# klon.net
KiCad netlist of a schematic drawn in EAGLE
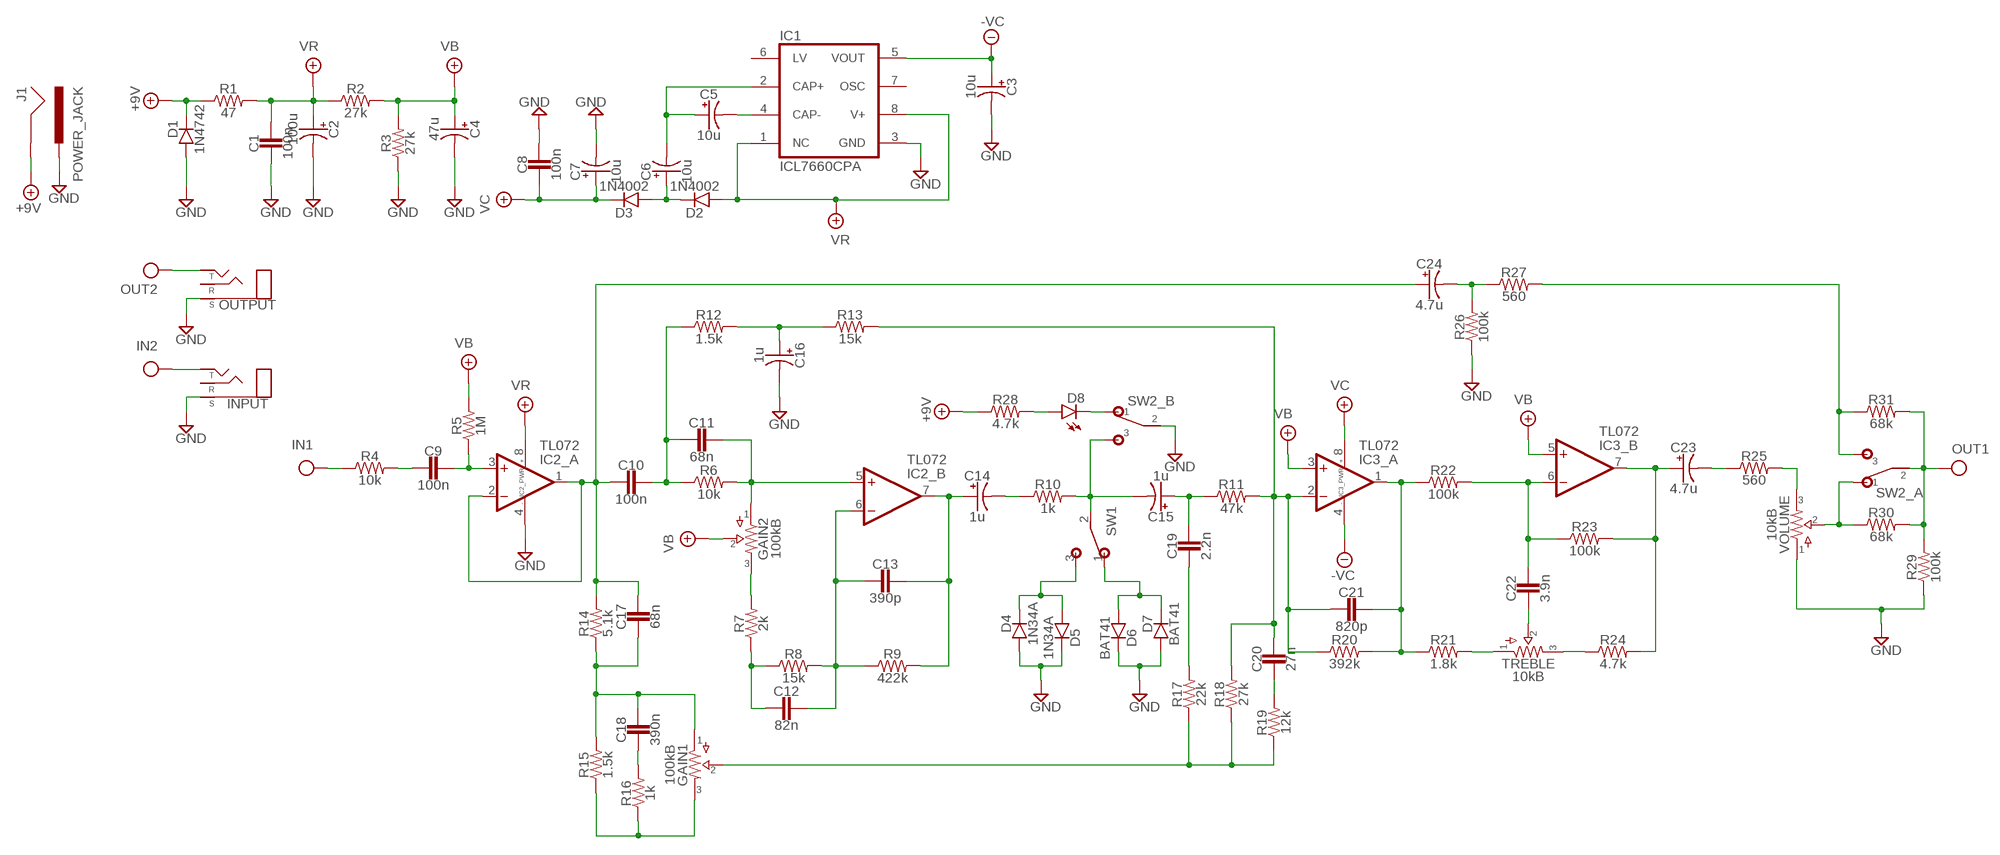
[diagram p0: schematic, sheet 1]

(export (version "E")
  (design (tool "Eeschema 10.0.6"))
  (components
    (comp (ref "C1")
      (value "100n")
      (footprint "eagle-import:050X030_025_2")
      (libsource (lib "eagle-import") (part "CER/FILM2"))
    )
    (comp (ref "C2")
      (value "100u")
      (footprint "eagle-import:050_020")
      (libsource (lib "eagle-import") (part "0500"))
    )
    (comp (ref "C3")
      (value "10u")
      (footprint "eagle-import:050_020")
      (libsource (lib "eagle-import") (part "0500"))
    )
    (comp (ref "C4")
      (value "47u")
      (footprint "eagle-import:050_020")
      (libsource (lib "eagle-import") (part "0500"))
    )
    (comp (ref "C5")
      (value "10u")
      (footprint "eagle-import:050_020")
      (libsource (lib "eagle-import") (part "0500"))
    )
    (comp (ref "C6")
      (value "10u")
      (footprint "eagle-import:050_020")
      (libsource (lib "eagle-import") (part "0500"))
    )
    (comp (ref "C7")
      (value "10u")
      (footprint "eagle-import:050_020")
      (libsource (lib "eagle-import") (part "0500"))
    )
    (comp (ref "C8")
      (value "100n")
      (footprint "eagle-import:050X030_025_2")
      (libsource (lib "eagle-import") (part "CER/FILM2"))
    )
    (comp (ref "C9")
      (value "100n")
      (footprint "eagle-import:BOX_SMALL")
      (libsource (lib "eagle-import") (part "CER/FILMBOX.1"))
    )
    (comp (ref "C10")
      (value "100n")
      (footprint "eagle-import:BOX_SMALL")
      (libsource (lib "eagle-import") (part "CER/FILMBOX.1"))
    )
    (comp (ref "C11")
      (value "68n")
      (footprint "eagle-import:BOX_SMALL")
      (libsource (lib "eagle-import") (part "CER/FILMBOX.1"))
    )
    (comp (ref "C12")
      (value "82n")
      (footprint "eagle-import:BOX_SMALL")
      (libsource (lib "eagle-import") (part "CER/FILMBOX.1"))
    )
    (comp (ref "C13")
      (value "390p")
      (footprint "eagle-import:050X030_025_2")
      (libsource (lib "eagle-import") (part "CER/FILM2"))
    )
    (comp (ref "C14")
      (value "1u")
      (footprint "eagle-import:040_020")
      (libsource (lib "eagle-import") (part "0400"))
    )
    (comp (ref "C15")
      (value "1u")
      (footprint "eagle-import:040_020")
      (libsource (lib "eagle-import") (part "0400"))
    )
    (comp (ref "C16")
      (value "1u")
      (footprint "eagle-import:040_020")
      (libsource (lib "eagle-import") (part "0400"))
    )
    (comp (ref "C17")
      (value "68n")
      (footprint "eagle-import:BOX_SMALL")
      (libsource (lib "eagle-import") (part "CER/FILMBOX.1"))
    )
    (comp (ref "C18")
      (value "390n")
      (footprint "eagle-import:BOX_MED")
      (libsource (lib "eagle-import") (part "CER/FILMBOX.2"))
    )
    (comp (ref "C19")
      (value "2.2n")
      (footprint "eagle-import:BOX_SMALL")
      (libsource (lib "eagle-import") (part "CER/FILMBOX.1"))
    )
    (comp (ref "C20")
      (value "27n")
      (footprint "eagle-import:BOX_SMALL")
      (libsource (lib "eagle-import") (part "CER/FILMBOX.1"))
    )
    (comp (ref "C21")
      (value "820p")
      (footprint "eagle-import:050X030_025_2")
      (libsource (lib "eagle-import") (part "CER/FILM2"))
    )
    (comp (ref "C22")
      (value "3.9n")
      (footprint "eagle-import:BOX_SMALL")
      (libsource (lib "eagle-import") (part "CER/FILMBOX.1"))
    )
    (comp (ref "C23")
      (value "4.7u")
      (footprint "eagle-import:050_020")
      (libsource (lib "eagle-import") (part "0500"))
    )
    (comp (ref "C24")
      (value "4.7u")
      (footprint "eagle-import:050_020")
      (libsource (lib "eagle-import") (part "0500"))
    )
    (comp (ref "D1")
      (value "1N4742")
      (footprint "eagle-import:DO41-2")
      (libsource (lib "eagle-import") (part "DO41.2"))
    )
    (comp (ref "D2")
      (value "1N4002")
      (footprint "eagle-import:DO41-2")
      (libsource (lib "eagle-import") (part "DO41.2"))
    )
    (comp (ref "D3")
      (value "1N4002")
      (footprint "eagle-import:DO41-2")
      (libsource (lib "eagle-import") (part "DO41.2"))
    )
    (comp (ref "D4")
      (value "1N34A")
      (footprint "eagle-import:DO35-2")
      (libsource (lib "eagle-import") (part "DO35.2"))
    )
    (comp (ref "D5")
      (value "1N34A")
      (footprint "eagle-import:DO35-2")
      (libsource (lib "eagle-import") (part "DO35.2"))
    )
    (comp (ref "D6")
      (value "BAT41")
      (footprint "eagle-import:DO35-2")
      (libsource (lib "eagle-import") (part "DO35.2"))
    )
    (comp (ref "D7")
      (value "BAT41")
      (footprint "eagle-import:DO35-2")
      (libsource (lib "eagle-import") (part "DO35.2"))
    )
    (comp (ref "D8")
      (value "LEDA")
      (footprint "eagle-import:3MM_A")
      (libsource (lib "eagle-import") (part "LEDA"))
    )
    (comp (ref "GAIN1")
      (value "100kB")
      (footprint "eagle-import:16MM")
      (libsource (lib "eagle-import") (part "POTS16MM"))
    )
    (comp (ref "GAIN2")
      (value "100kB")
      (footprint "eagle-import:16MM")
      (libsource (lib "eagle-import") (part "POTS16MM"))
    )
    (comp (ref "IC1")
      (value "ICL7660CPA")
      (footprint "eagle-import:DIL08")
      (fields (field (name "MF") "INTERSIL"))
      (libsource (lib "eagle-import") (part "ICL7660CPA"))
    )
    (comp (ref "IC2")
      (value "TL072")
      (footprint "eagle-import:DIL0")
      (libsource (lib "eagle-import") (part "DUALTH"))
    )
    (comp (ref "IC3")
      (value "TL072")
      (footprint "eagle-import:DIL0")
      (libsource (lib "eagle-import") (part "DUALTH"))
    )
    (comp (ref "INPUT")
      (value "STEREONMJ")
      (footprint "eagle-import:NMJ6HCD2")
      (libsource (lib "eagle-import") (part "STEREONMJ"))
    )
    (comp (ref "J1")
      (value "POWER_JACK")
      (footprint "eagle-import:POWER_JACK_PTH")
      (libsource (lib "eagle-import") (part "POWER_JACK"))
    )
    (comp (ref "OUTPUT")
      (value "STEREONMJ")
      (footprint "eagle-import:NMJ6HCD2")
      (libsource (lib "eagle-import") (part "STEREONMJ"))
    )
    (comp (ref "R1")
      (value "47")
      (footprint "eagle-import:R0207_3")
      (libsource (lib "eagle-import") (part "R_.3B"))
    )
    (comp (ref "R2")
      (value "27k")
      (footprint "eagle-import:R0207_3")
      (libsource (lib "eagle-import") (part "R_.3B"))
    )
    (comp (ref "R3")
      (value "27k")
      (footprint "eagle-import:R0207_3")
      (libsource (lib "eagle-import") (part "R_.3B"))
    )
    (comp (ref "R4")
      (value "10k")
      (footprint "eagle-import:R0207_3")
      (libsource (lib "eagle-import") (part "R_.3B"))
    )
    (comp (ref "R5")
      (value "1M")
      (footprint "eagle-import:R0207_3")
      (libsource (lib "eagle-import") (part "R_.3B"))
    )
    (comp (ref "R6")
      (value "10k")
      (footprint "eagle-import:R0207_3")
      (libsource (lib "eagle-import") (part "R_.3B"))
    )
    (comp (ref "R7")
      (value "2k")
      (footprint "eagle-import:R0207_3")
      (libsource (lib "eagle-import") (part "R_.3B"))
    )
    (comp (ref "R8")
      (value "15k")
      (footprint "eagle-import:R0207_3")
      (libsource (lib "eagle-import") (part "R_.3B"))
    )
    (comp (ref "R9")
      (value "422k")
      (footprint "eagle-import:R0207_3")
      (libsource (lib "eagle-import") (part "R_.3B"))
    )
    (comp (ref "R10")
      (value "1k")
      (footprint "eagle-import:R0207_3")
      (libsource (lib "eagle-import") (part "R_.3B"))
    )
    (comp (ref "R11")
      (value "47k")
      (footprint "eagle-import:R0207_3")
      (libsource (lib "eagle-import") (part "R_.3B"))
    )
    (comp (ref "R12")
      (value "1.5k")
      (footprint "eagle-import:R0207_3")
      (libsource (lib "eagle-import") (part "R_.3B"))
    )
    (comp (ref "R13")
      (value "15k")
      (footprint "eagle-import:R0207_3")
      (libsource (lib "eagle-import") (part "R_.3B"))
    )
    (comp (ref "R14")
      (value "5.1k")
      (footprint "eagle-import:R0207_3")
      (libsource (lib "eagle-import") (part "R_.3B"))
    )
    (comp (ref "R15")
      (value "1.5k")
      (footprint "eagle-import:R0207_3")
      (libsource (lib "eagle-import") (part "R_.3B"))
    )
    (comp (ref "R16")
      (value "1k")
      (footprint "eagle-import:R0207_3")
      (libsource (lib "eagle-import") (part "R_.3B"))
    )
    (comp (ref "R17")
      (value "22k")
      (footprint "eagle-import:R0207_3")
      (libsource (lib "eagle-import") (part "R_.3B"))
    )
    (comp (ref "R18")
      (value "27k")
      (footprint "eagle-import:R0207_3")
      (libsource (lib "eagle-import") (part "R_.3B"))
    )
    (comp (ref "R19")
      (value "12k")
      (footprint "eagle-import:R0207_3")
      (libsource (lib "eagle-import") (part "R_.3B"))
    )
    (comp (ref "R20")
      (value "392k")
      (footprint "eagle-import:R0207_3")
      (libsource (lib "eagle-import") (part "R_.3B"))
    )
    (comp (ref "R21")
      (value "1.8k")
      (footprint "eagle-import:R0207_3")
      (libsource (lib "eagle-import") (part "R_.3B"))
    )
    (comp (ref "R22")
      (value "100k")
      (footprint "eagle-import:R0207_3")
      (libsource (lib "eagle-import") (part "R_.3B"))
    )
    (comp (ref "R23")
      (value "100k")
      (footprint "eagle-import:R0207_3")
      (libsource (lib "eagle-import") (part "R_.3B"))
    )
    (comp (ref "R24")
      (value "4.7k")
      (footprint "eagle-import:R0207_3")
      (libsource (lib "eagle-import") (part "R_.3B"))
    )
    (comp (ref "R25")
      (value "560")
      (footprint "eagle-import:R0207_3")
      (libsource (lib "eagle-import") (part "R_.3B"))
    )
    (comp (ref "R26")
      (value "100k")
      (footprint "eagle-import:R0207_3")
      (libsource (lib "eagle-import") (part "R_.3B"))
    )
    (comp (ref "R27")
      (value "560")
      (footprint "eagle-import:R0207_3")
      (libsource (lib "eagle-import") (part "R_.3B"))
    )
    (comp (ref "R28")
      (value "4.7k")
      (footprint "eagle-import:R0207_3")
      (libsource (lib "eagle-import") (part "R_.3B"))
    )
    (comp (ref "R29")
      (value "100k")
      (footprint "eagle-import:R0207_3")
      (libsource (lib "eagle-import") (part "R_.3B"))
    )
    (comp (ref "R30")
      (value "68k")
      (footprint "eagle-import:R0207_3")
      (libsource (lib "eagle-import") (part "R_.3B"))
    )
    (comp (ref "R31")
      (value "68k")
      (footprint "eagle-import:R0207_3")
      (libsource (lib "eagle-import") (part "R_.3B"))
    )
    (comp (ref "SW1")
      (value "SPDT")
      (footprint "eagle-import:M9040P")
      (libsource (lib "eagle-import") (part "SPDT"))
    )
    (comp (ref "SW2")
      (value "DPDTPADS")
      (footprint "eagle-import:DPDT_PADS")
      (libsource (lib "eagle-import") (part "DPDTPADS"))
    )
    (comp (ref "TREBLE")
      (value "10kB")
      (footprint "eagle-import:16MM")
      (libsource (lib "eagle-import") (part "POTS16MM"))
    )
    (comp (ref "VOLUME")
      (value "10kB")
      (footprint "eagle-import:16MM")
      (libsource (lib "eagle-import") (part "POTS16MM"))
    )
  )
  (nets
    (net (code "1") (name "+9V") (class "Default")
      (node (ref "D1") (pin "C") (pinfunction "C_C") (pintype "passive"))
      (node (ref "J1") (pin "GND") (pinfunction "GND_GND") (pintype "bidirectional"))
      (node (ref "R1") (pin "1") (pinfunction "1_1") (pintype "passive"))
      (node (ref "R28") (pin "1") (pinfunction "1_1") (pintype "passive"))
    )
    (net (code "2") (name "-VC") (class "Default")
      (node (ref "C3") (pin "+") (pinfunction "+_+") (pintype "passive"))
      (node (ref "IC1") (pin "5") (pinfunction "VOUT_5") (pintype "power_in"))
      (node (ref "IC3") (pin "4") (pinfunction "V-_4") (pintype "power_in"))
    )
    (net (code "3") (name "GND") (class "Default")
      (node (ref "C1") (pin "2") (pinfunction "2_2") (pintype "passive"))
      (node (ref "C16") (pin "-") (pinfunction "-_-") (pintype "passive"))
      (node (ref "C2") (pin "-") (pinfunction "-_-") (pintype "passive"))
      (node (ref "C3") (pin "-") (pinfunction "-_-") (pintype "passive"))
      (node (ref "C4") (pin "-") (pinfunction "-_-") (pintype "passive"))
      (node (ref "C7") (pin "-") (pinfunction "-_-") (pintype "passive"))
      (node (ref "C8") (pin "1") (pinfunction "1_1") (pintype "passive"))
      (node (ref "D1") (pin "A") (pinfunction "A_A") (pintype "passive"))
      (node (ref "D4") (pin "A") (pinfunction "A_A") (pintype "passive"))
      (node (ref "D5") (pin "C") (pinfunction "C_C") (pintype "passive"))
      (node (ref "D6") (pin "C") (pinfunction "C_C") (pintype "passive"))
      (node (ref "D7") (pin "A") (pinfunction "A_A") (pintype "passive"))
      (node (ref "IC1") (pin "3") (pinfunction "GND_3") (pintype "power_in"))
      (node (ref "IC2") (pin "4") (pinfunction "V-_4") (pintype "power_in"))
      (node (ref "INPUT") (pin "S") (pinfunction "S_S") (pintype "passive"))
      (node (ref "J1") (pin "PWR") (pinfunction "PWR_PWR") (pintype "bidirectional"))
      (node (ref "OUTPUT") (pin "S") (pinfunction "S_S") (pintype "passive"))
      (node (ref "R26") (pin "1") (pinfunction "1_1") (pintype "passive"))
      (node (ref "R29") (pin "1") (pinfunction "1_1") (pintype "passive"))
      (node (ref "R3") (pin "1") (pinfunction "1_1") (pintype "passive"))
      (node (ref "SW2") (pin "P$5") (pinfunction "2_P$5") (pintype "passive"))
      (node (ref "VOLUME") (pin "1") (pinfunction "1_1") (pintype "passive"))
    )
    (net (code "4") (name "IN") (class "Default")
      (node (ref "INPUT") (pin "T") (pinfunction "T_T") (pintype "passive"))
      (node (ref "R4") (pin "1") (pinfunction "1_1") (pintype "passive"))
    )
    (net (code "5") (name "Net-(C6-Pad+)") (class "Default")
      (node (ref "C6") (pin "+") (pinfunction "+_+") (pintype "passive"))
      (node (ref "D2") (pin "C") (pinfunction "C_C") (pintype "passive"))
      (node (ref "D3") (pin "A") (pinfunction "A_A") (pintype "passive"))
    )
    (net (code "6") (name "Net-(C9-Pad2)") (class "Default")
      (node (ref "C9") (pin "2") (pinfunction "2_2") (pintype "passive"))
      (node (ref "R4") (pin "2") (pinfunction "2_2") (pintype "passive"))
    )
    (net (code "7") (name "Net-(C10-Pad1)") (class "Default")
      (node (ref "C10") (pin "1") (pinfunction "1_1") (pintype "passive"))
      (node (ref "C11") (pin "2") (pinfunction "2_2") (pintype "passive"))
      (node (ref "R12") (pin "1") (pinfunction "1_1") (pintype "passive"))
      (node (ref "R6") (pin "1") (pinfunction "1_1") (pintype "passive"))
    )
    (net (code "8") (name "Net-(C12-Pad2)") (class "Default")
      (node (ref "C12") (pin "2") (pinfunction "2_2") (pintype "passive"))
      (node (ref "R7") (pin "1") (pinfunction "1_1") (pintype "passive"))
      (node (ref "R8") (pin "1") (pinfunction "1_1") (pintype "passive"))
    )
    (net (code "9") (name "Net-(C14-Pad-)") (class "Default")
      (node (ref "C14") (pin "-") (pinfunction "-_-") (pintype "passive"))
      (node (ref "R10") (pin "1") (pinfunction "1_1") (pintype "passive"))
    )
    (net (code "10") (name "Net-(C15-Pad+)") (class "Default")
      (node (ref "C15") (pin "+") (pinfunction "+_+") (pintype "passive"))
      (node (ref "C19") (pin "1") (pinfunction "1_1") (pintype "passive"))
      (node (ref "R11") (pin "1") (pinfunction "1_1") (pintype "passive"))
    )
    (net (code "11") (name "Net-(C16-Pad+)") (class "Default")
      (node (ref "C16") (pin "+") (pinfunction "+_+") (pintype "passive"))
      (node (ref "R12") (pin "2") (pinfunction "2_2") (pintype "passive"))
      (node (ref "R13") (pin "1") (pinfunction "1_1") (pintype "passive"))
    )
    (net (code "12") (name "Net-(C17-Pad2)") (class "Default")
      (node (ref "C17") (pin "2") (pinfunction "2_2") (pintype "passive"))
      (node (ref "C18") (pin "1") (pinfunction "1_1") (pintype "passive"))
      (node (ref "GAIN1") (pin "1") (pinfunction "1_1") (pintype "passive"))
      (node (ref "R14") (pin "1") (pinfunction "1_1") (pintype "passive"))
      (node (ref "R15") (pin "2") (pinfunction "2_2") (pintype "passive"))
    )
    (net (code "13") (name "Net-(C18-Pad2)") (class "Default")
      (node (ref "C18") (pin "2") (pinfunction "2_2") (pintype "passive"))
      (node (ref "R16") (pin "2") (pinfunction "2_2") (pintype "passive"))
    )
    (net (code "14") (name "Net-(C19-Pad2)") (class "Default")
      (node (ref "C19") (pin "2") (pinfunction "2_2") (pintype "passive"))
      (node (ref "R17") (pin "2") (pinfunction "2_2") (pintype "passive"))
    )
    (net (code "15") (name "Net-(C20-Pad2)") (class "Default")
      (node (ref "C20") (pin "2") (pinfunction "2_2") (pintype "passive"))
      (node (ref "R19") (pin "2") (pinfunction "2_2") (pintype "passive"))
    )
    (net (code "16") (name "Net-(C22-Pad2)") (class "Default")
      (node (ref "C22") (pin "2") (pinfunction "2_2") (pintype "passive"))
      (node (ref "TREBLE") (pin "2") (pinfunction "2_2") (pintype "passive"))
    )
    (net (code "17") (name "Net-(C23-Pad-)") (class "Default")
      (node (ref "C23") (pin "-") (pinfunction "-_-") (pintype "passive"))
      (node (ref "R25") (pin "1") (pinfunction "1_1") (pintype "passive"))
    )
    (net (code "18") (name "Net-(C24-Pad-)") (class "Default")
      (node (ref "C24") (pin "-") (pinfunction "-_-") (pintype "passive"))
      (node (ref "R26") (pin "2") (pinfunction "2_2") (pintype "passive"))
      (node (ref "R27") (pin "1") (pinfunction "1_1") (pintype "passive"))
    )
    (net (code "19") (name "Net-(D8-C)") (class "Default")
      (node (ref "D8") (pin "K") (pinfunction "C_K") (pintype "passive"))
      (node (ref "SW2") (pin "P$4") (pinfunction "1_P$4") (pintype "passive"))
    )
    (net (code "20") (name "Net-(D8-PadA)") (class "Default")
      (node (ref "D8") (pin "A") (pinfunction "A_A") (pintype "passive"))
      (node (ref "R28") (pin "2") (pinfunction "2_2") (pintype "passive"))
    )
    (net (code "21") (name "Net-(GAIN1-Pad2)") (class "Default")
      (node (ref "GAIN1") (pin "2") (pinfunction "2_2") (pintype "passive"))
      (node (ref "R17") (pin "1") (pinfunction "1_1") (pintype "passive"))
      (node (ref "R18") (pin "1") (pinfunction "1_1") (pintype "passive"))
      (node (ref "R19") (pin "1") (pinfunction "1_1") (pintype "passive"))
    )
    (net (code "22") (name "Net-(GAIN1-Pad3)") (class "Default")
      (node (ref "GAIN1") (pin "3") (pinfunction "3_3") (pintype "passive"))
      (node (ref "R15") (pin "1") (pinfunction "1_1") (pintype "passive"))
      (node (ref "R16") (pin "1") (pinfunction "1_1") (pintype "passive"))
    )
    (net (code "23") (name "Net-(GAIN2-Pad3)") (class "Default")
      (node (ref "GAIN2") (pin "3") (pinfunction "3_3") (pintype "passive"))
      (node (ref "R7") (pin "2") (pinfunction "2_2") (pintype "passive"))
    )
    (net (code "24") (name "Net-(IC1-CAP+)") (class "Default")
      (node (ref "C5") (pin "+") (pinfunction "+_+") (pintype "passive"))
      (node (ref "C6") (pin "-") (pinfunction "-_-") (pintype "passive"))
      (node (ref "IC1") (pin "2") (pinfunction "CAP+_2") (pintype "passive"))
    )
    (net (code "25") (name "Net-(IC1-CAP-)") (class "Default")
      (node (ref "C5") (pin "-") (pinfunction "-_-") (pintype "passive"))
      (node (ref "IC1") (pin "4") (pinfunction "CAP-_4") (pintype "passive"))
    )
    (net (code "26") (name "Net-(IC2A-+IN)") (class "Default")
      (node (ref "C9") (pin "1") (pinfunction "1_1") (pintype "passive"))
      (node (ref "IC2") (pin "3") (pinfunction "+IN_3") (pintype "input"))
      (node (ref "R5") (pin "1") (pinfunction "1_1") (pintype "passive"))
    )
    (net (code "27") (name "Net-(IC2A--IN)") (class "Default")
      (node (ref "C10") (pin "2") (pinfunction "2_2") (pintype "passive"))
      (node (ref "C17") (pin "1") (pinfunction "1_1") (pintype "passive"))
      (node (ref "C24") (pin "+") (pinfunction "+_+") (pintype "passive"))
      (node (ref "IC2") (pin "1") (pinfunction "OUT_1") (pintype "output"))
      (node (ref "IC2") (pin "2") (pinfunction "-IN_2") (pintype "input"))
      (node (ref "R14") (pin "2") (pinfunction "2_2") (pintype "passive"))
    )
    (net (code "28") (name "Net-(IC2B-+IN)") (class "Default")
      (node (ref "C11") (pin "1") (pinfunction "1_1") (pintype "passive"))
      (node (ref "GAIN2") (pin "1") (pinfunction "1_1") (pintype "passive"))
      (node (ref "IC2") (pin "5") (pinfunction "+IN_5") (pintype "input"))
      (node (ref "R6") (pin "2") (pinfunction "2_2") (pintype "passive"))
    )
    (net (code "29") (name "Net-(IC2B--IN)") (class "Default")
      (node (ref "C12") (pin "1") (pinfunction "1_1") (pintype "passive"))
      (node (ref "C13") (pin "2") (pinfunction "2_2") (pintype "passive"))
      (node (ref "IC2") (pin "6") (pinfunction "-IN_6") (pintype "input"))
      (node (ref "R8") (pin "2") (pinfunction "2_2") (pintype "passive"))
      (node (ref "R9") (pin "1") (pinfunction "1_1") (pintype "passive"))
    )
    (net (code "30") (name "Net-(IC2B-OUT)") (class "Default")
      (node (ref "C13") (pin "1") (pinfunction "1_1") (pintype "passive"))
      (node (ref "C14") (pin "+") (pinfunction "+_+") (pintype "passive"))
      (node (ref "IC2") (pin "7") (pinfunction "OUT_7") (pintype "output"))
      (node (ref "R9") (pin "2") (pinfunction "2_2") (pintype "passive"))
    )
    (net (code "31") (name "Net-(IC3A--IN)") (class "Default")
      (node (ref "C20") (pin "1") (pinfunction "1_1") (pintype "passive"))
      (node (ref "C21") (pin "2") (pinfunction "2_2") (pintype "passive"))
      (node (ref "IC3") (pin "2") (pinfunction "-IN_2") (pintype "input"))
      (node (ref "R11") (pin "2") (pinfunction "2_2") (pintype "passive"))
      (node (ref "R13") (pin "2") (pinfunction "2_2") (pintype "passive"))
      (node (ref "R18") (pin "2") (pinfunction "2_2") (pintype "passive"))
      (node (ref "R20") (pin "1") (pinfunction "1_1") (pintype "passive"))
    )
    (net (code "32") (name "Net-(IC3A-OUT)") (class "Default")
      (node (ref "C21") (pin "1") (pinfunction "1_1") (pintype "passive"))
      (node (ref "IC3") (pin "1") (pinfunction "OUT_1") (pintype "output"))
      (node (ref "R20") (pin "2") (pinfunction "2_2") (pintype "passive"))
      (node (ref "R21") (pin "1") (pinfunction "1_1") (pintype "passive"))
      (node (ref "R22") (pin "1") (pinfunction "1_1") (pintype "passive"))
    )
    (net (code "33") (name "Net-(IC3B--IN)") (class "Default")
      (node (ref "C22") (pin "1") (pinfunction "1_1") (pintype "passive"))
      (node (ref "IC3") (pin "6") (pinfunction "-IN_6") (pintype "input"))
      (node (ref "R22") (pin "2") (pinfunction "2_2") (pintype "passive"))
      (node (ref "R23") (pin "1") (pinfunction "1_1") (pintype "passive"))
    )
    (net (code "34") (name "Net-(IC3B-OUT)") (class "Default")
      (node (ref "C23") (pin "+") (pinfunction "+_+") (pintype "passive"))
      (node (ref "IC3") (pin "7") (pinfunction "OUT_7") (pintype "output"))
      (node (ref "R23") (pin "2") (pinfunction "2_2") (pintype "passive"))
      (node (ref "R24") (pin "2") (pinfunction "2_2") (pintype "passive"))
    )
    (net (code "35") (name "Net-(R21-Pad2)") (class "Default")
      (node (ref "R21") (pin "2") (pinfunction "2_2") (pintype "passive"))
      (node (ref "TREBLE") (pin "1") (pinfunction "1_1") (pintype "passive"))
    )
    (net (code "36") (name "Net-(R24-Pad1)") (class "Default")
      (node (ref "R24") (pin "1") (pinfunction "1_1") (pintype "passive"))
      (node (ref "TREBLE") (pin "3") (pinfunction "3_3") (pintype "passive"))
    )
    (net (code "37") (name "Net-(R25-Pad2)") (class "Default")
      (node (ref "R25") (pin "2") (pinfunction "2_2") (pintype "passive"))
      (node (ref "VOLUME") (pin "3") (pinfunction "3_3") (pintype "passive"))
    )
    (net (code "38") (name "Net-(SW1-O)") (class "Default")
      (node (ref "D6") (pin "A") (pinfunction "A_A") (pintype "passive"))
      (node (ref "D7") (pin "C") (pinfunction "C_C") (pintype "passive"))
      (node (ref "SW1") (pin "1") (pinfunction "O_1") (pintype "passive"))
    )
    (net (code "39") (name "Net-(SW1-P)") (class "Default")
      (node (ref "C15") (pin "-") (pinfunction "-_-") (pintype "passive"))
      (node (ref "R10") (pin "2") (pinfunction "2_2") (pintype "passive"))
      (node (ref "SW1") (pin "2") (pinfunction "P_2") (pintype "passive"))
      (node (ref "SW2") (pin "P$6") (pinfunction "3_P$6") (pintype "passive"))
    )
    (net (code "40") (name "Net-(SW1-S)") (class "Default")
      (node (ref "D4") (pin "C") (pinfunction "C_C") (pintype "passive"))
      (node (ref "D5") (pin "A") (pinfunction "A_A") (pintype "passive"))
      (node (ref "SW1") (pin "3") (pinfunction "S_3") (pintype "passive"))
    )
    (net (code "41") (name "Net-(SW2A-1)") (class "Default")
      (node (ref "R30") (pin "1") (pinfunction "1_1") (pintype "passive"))
      (node (ref "SW2") (pin "P$1") (pinfunction "1_P$1") (pintype "passive"))
      (node (ref "VOLUME") (pin "2") (pinfunction "2_2") (pintype "passive"))
    )
    (net (code "42") (name "Net-(SW2A-3)") (class "Default")
      (node (ref "R27") (pin "2") (pinfunction "2_2") (pintype "passive"))
      (node (ref "R31") (pin "1") (pinfunction "1_1") (pintype "passive"))
      (node (ref "SW2") (pin "P$3") (pinfunction "3_P$3") (pintype "passive"))
    )
    (net (code "43") (name "OUT") (class "Default")
      (node (ref "OUTPUT") (pin "T") (pinfunction "T_T") (pintype "passive"))
      (node (ref "R29") (pin "2") (pinfunction "2_2") (pintype "passive"))
      (node (ref "R30") (pin "2") (pinfunction "2_2") (pintype "passive"))
      (node (ref "R31") (pin "2") (pinfunction "2_2") (pintype "passive"))
      (node (ref "SW2") (pin "P$2") (pinfunction "2_P$2") (pintype "passive"))
    )
    (net (code "44") (name "VB") (class "Default")
      (node (ref "C4") (pin "+") (pinfunction "+_+") (pintype "passive"))
      (node (ref "GAIN2") (pin "2") (pinfunction "2_2") (pintype "passive"))
      (node (ref "IC3") (pin "3") (pinfunction "+IN_3") (pintype "input"))
      (node (ref "IC3") (pin "5") (pinfunction "+IN_5") (pintype "input"))
      (node (ref "R2") (pin "2") (pinfunction "2_2") (pintype "passive"))
      (node (ref "R3") (pin "2") (pinfunction "2_2") (pintype "passive"))
      (node (ref "R5") (pin "2") (pinfunction "2_2") (pintype "passive"))
    )
    (net (code "45") (name "VC") (class "Default")
      (node (ref "C7") (pin "+") (pinfunction "+_+") (pintype "passive"))
      (node (ref "C8") (pin "2") (pinfunction "2_2") (pintype "passive"))
      (node (ref "D3") (pin "C") (pinfunction "C_C") (pintype "passive"))
      (node (ref "IC3") (pin "8") (pinfunction "V+_8") (pintype "power_in"))
    )
    (net (code "46") (name "VR") (class "Default")
      (node (ref "C1") (pin "1") (pinfunction "1_1") (pintype "passive"))
      (node (ref "C2") (pin "+") (pinfunction "+_+") (pintype "passive"))
      (node (ref "D2") (pin "A") (pinfunction "A_A") (pintype "passive"))
      (node (ref "IC1") (pin "1") (pinfunction "NC_1") (pintype "power_in"))
      (node (ref "IC1") (pin "8") (pinfunction "V+_8") (pintype "power_in"))
      (node (ref "IC2") (pin "8") (pinfunction "V+_8") (pintype "power_in"))
      (node (ref "R1") (pin "2") (pinfunction "2_2") (pintype "passive"))
      (node (ref "R2") (pin "1") (pinfunction "1_1") (pintype "passive"))
    )
    (net (code "47") (name "unconnected-(IC1-LV-Pad6)") (class "Default")
      (node (ref "IC1") (pin "6") (pinfunction "LV_6") (pintype "passive"))
    )
    (net (code "48") (name "unconnected-(IC1-OSC-Pad7)") (class "Default")
      (node (ref "IC1") (pin "7") (pinfunction "OSC_7") (pintype "output"))
    )
    (net (code "49") (name "unconnected-(INPUT-PadR)") (class "Default")
      (node (ref "INPUT") (pin "R") (pinfunction "R_R") (pintype "passive"))
    )
    (net (code "50") (name "unconnected-(OUTPUT-PadR)") (class "Default")
      (node (ref "OUTPUT") (pin "R") (pinfunction "R_R") (pintype "passive"))
    )
  )
)
